# LasaurDriverBoard2.net
KiCad netlist of a schematic drawn in EAGLE
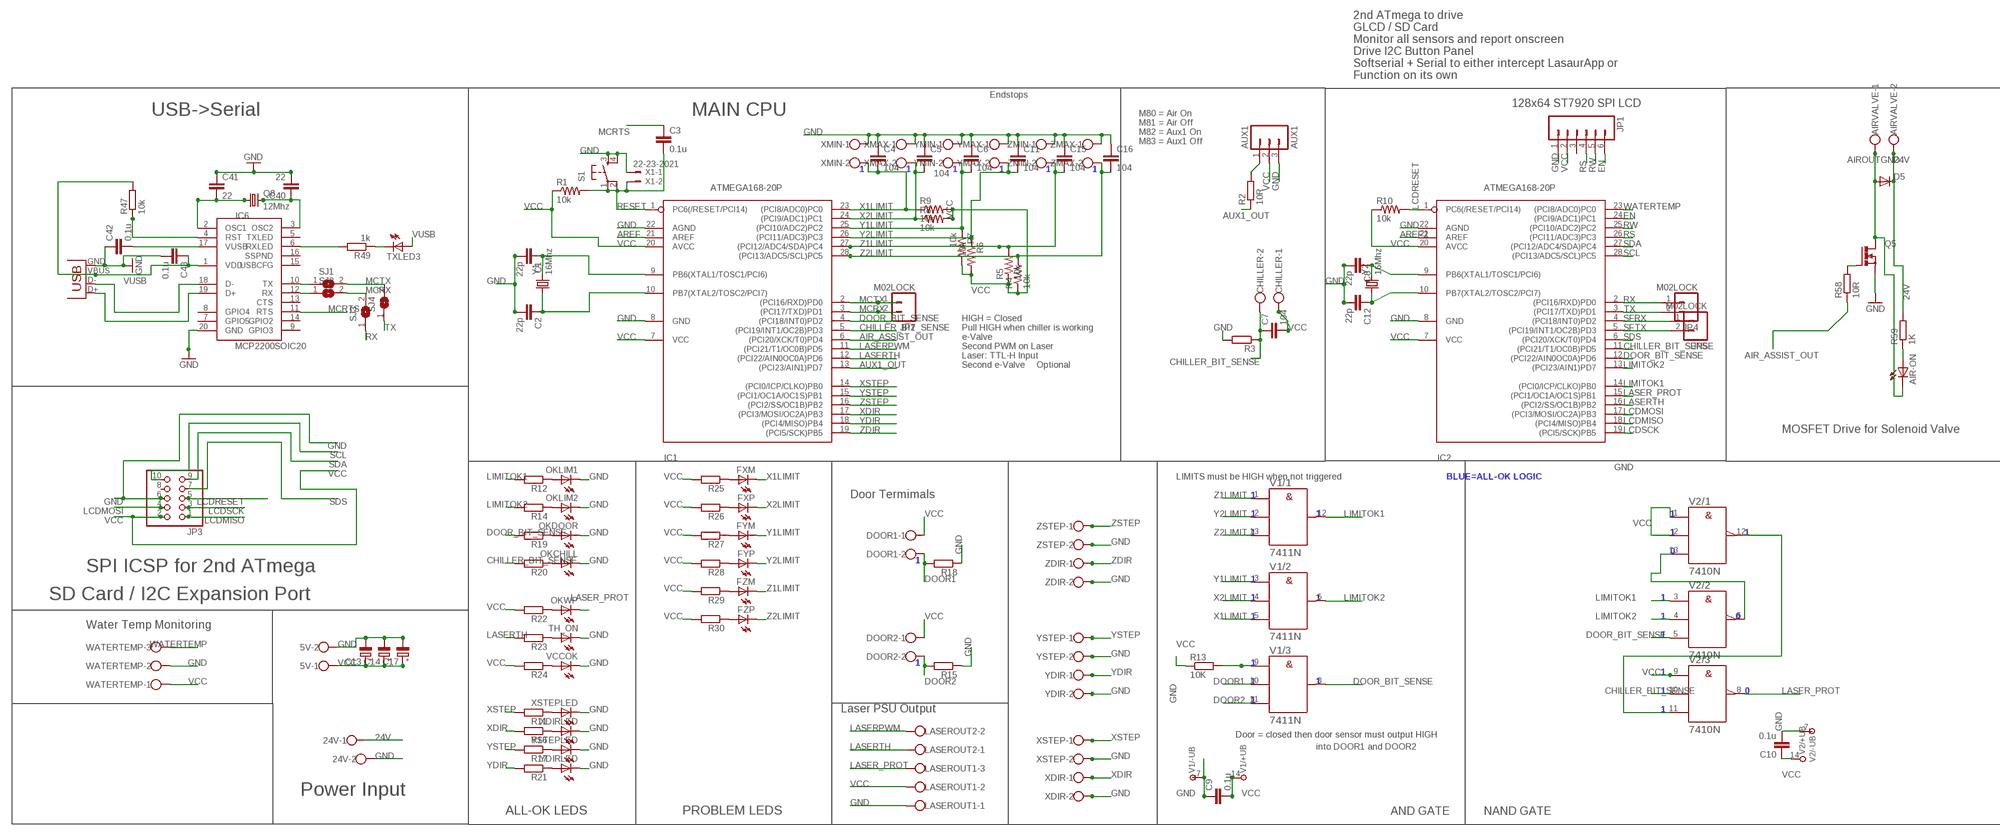
[diagram p0: schematic, sheet 1, part 1 of 2]
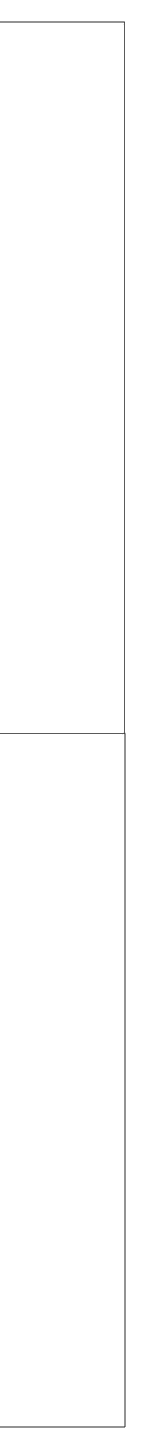
[diagram p1: schematic, sheet 1, part 2 of 2]

(export (version "E")
  (design (tool "Eeschema 10.0.6"))
  (components
    (comp (ref "5V")
      (value "W237-102")
      (footprint "eagle-import:W237-102")
      (fields (field (name "MPN") "237-102"))
      (libsource (lib "eagle-import") (part "W237-102"))
    )
    (comp (ref "24V")
      (value "W237-102")
      (footprint "eagle-import:W237-102")
      (fields (field (name "MPN") "237-102"))
      (libsource (lib "eagle-import") (part "W237-102"))
    )
    (comp (ref "AIR-ON")
      (value "LED3MM")
      (footprint "eagle-import:LED3MM")
      (libsource (lib "eagle-import") (part "LED3MM"))
    )
    (comp (ref "AIRVALVE")
      (value "W237-102")
      (footprint "eagle-import:W237-102")
      (fields (field (name "MPN") "237-102"))
      (libsource (lib "eagle-import") (part "W237-102"))
    )
    (comp (ref "AUX1")
      (value "AUX1")
      (footprint "eagle-import:MOLEX-1X3")
      (libsource (lib "eagle-import") (part "M03POLAR"))
    )
    (comp (ref "C1")
      (value "22p")
      (footprint "eagle-import:1206")
      (libsource (lib "eagle-import") (part "CAP1206"))
    )
    (comp (ref "C2")
      (value "22p")
      (footprint "eagle-import:1206")
      (libsource (lib "eagle-import") (part "CAP1206"))
    )
    (comp (ref "C3")
      (value "0.1u")
      (footprint "eagle-import:1206")
      (libsource (lib "eagle-import") (part "CAP1206"))
    )
    (comp (ref "C4")
      (value "104")
      (footprint "eagle-import:C1206")
      (libsource (lib "eagle-import") (part "C-EUC1206"))
    )
    (comp (ref "C5")
      (value "C-EUC1206")
      (footprint "eagle-import:C1206")
      (libsource (lib "eagle-import") (part "C-EUC1206"))
    )
    (comp (ref "C6")
      (value "104")
      (footprint "eagle-import:C1206")
      (libsource (lib "eagle-import") (part "C-EUC1206"))
    )
    (comp (ref "C7")
      (value "104")
      (footprint "eagle-import:C1206")
      (libsource (lib "eagle-import") (part "C-EUC1206"))
    )
    (comp (ref "C8")
      (value "22p")
      (footprint "eagle-import:1206")
      (libsource (lib "eagle-import") (part "CAP1206"))
    )
    (comp (ref "C9")
      (value "0.1u")
      (footprint "eagle-import:1206")
      (libsource (lib "eagle-import") (part "CAP1206"))
    )
    (comp (ref "C10")
      (value "0.1u")
      (footprint "eagle-import:1206")
      (libsource (lib "eagle-import") (part "CAP1206"))
    )
    (comp (ref "C11")
      (value "104")
      (footprint "eagle-import:C1206")
      (libsource (lib "eagle-import") (part "C-EUC1206"))
    )
    (comp (ref "C12")
      (value "22p")
      (footprint "eagle-import:1206")
      (libsource (lib "eagle-import") (part "CAP1206"))
    )
    (comp (ref "C13")
      (value "CPOL-EUB")
      (footprint "eagle-import:PANASONIC_B")
      (libsource (lib "eagle-import") (part "CPOL-EUB"))
    )
    (comp (ref "C14")
      (value "CPOL-EUB")
      (footprint "eagle-import:PANASONIC_B")
      (libsource (lib "eagle-import") (part "CPOL-EUB"))
    )
    (comp (ref "C15")
      (value "104")
      (footprint "eagle-import:C1206")
      (libsource (lib "eagle-import") (part "C-EUC1206"))
    )
    (comp (ref "C16")
      (value "104")
      (footprint "eagle-import:C1206")
      (libsource (lib "eagle-import") (part "C-EUC1206"))
    )
    (comp (ref "C17")
      (value "CPOL-EUB")
      (footprint "eagle-import:PANASONIC_B")
      (libsource (lib "eagle-import") (part "CPOL-EUB"))
    )
    (comp (ref "C40")
      (value "22")
      (footprint "eagle-import:1206")
      (libsource (lib "eagle-import") (part "CAP1206"))
    )
    (comp (ref "C41")
      (value "22")
      (footprint "eagle-import:1206")
      (libsource (lib "eagle-import") (part "CAP1206"))
    )
    (comp (ref "C42")
      (value "0.1u")
      (footprint "eagle-import:1206")
      (libsource (lib "eagle-import") (part "CAP1206"))
    )
    (comp (ref "C43")
      (value "0.1u")
      (footprint "eagle-import:1206")
      (libsource (lib "eagle-import") (part "CAP1206"))
    )
    (comp (ref "CHILLER")
      (value "W237-102")
      (footprint "eagle-import:W237-102")
      (fields (field (name "MPN") "237-102"))
      (libsource (lib "eagle-import") (part "W237-102"))
    )
    (comp (ref "D5")
      (value "DIODESMA-ALT")
      (footprint "eagle-import:SMA-DIODE_ALT")
      (libsource (lib "eagle-import") (part "DIODESMA-ALT"))
    )
    (comp (ref "DOOR1")
      (value "W237-102")
      (footprint "eagle-import:W237-102")
      (fields (field (name "MPN") "237-102"))
      (libsource (lib "eagle-import") (part "W237-102"))
    )
    (comp (ref "DOOR2")
      (value "W237-102")
      (footprint "eagle-import:W237-102")
      (fields (field (name "MPN") "237-102"))
      (libsource (lib "eagle-import") (part "W237-102"))
    )
    (comp (ref "FXM")
      (value "LED3MM")
      (footprint "eagle-import:LED3MM")
      (libsource (lib "eagle-import") (part "led_LED3MM"))
    )
    (comp (ref "FXP")
      (value "LED3MM")
      (footprint "eagle-import:LED3MM")
      (libsource (lib "eagle-import") (part "led_LED3MM"))
    )
    (comp (ref "FYM")
      (value "LED3MM")
      (footprint "eagle-import:LED3MM")
      (libsource (lib "eagle-import") (part "led_LED3MM"))
    )
    (comp (ref "FYP")
      (value "LED3MM")
      (footprint "eagle-import:LED3MM")
      (libsource (lib "eagle-import") (part "led_LED3MM"))
    )
    (comp (ref "FZM")
      (value "LED3MM")
      (footprint "eagle-import:LED3MM")
      (libsource (lib "eagle-import") (part "led_LED3MM"))
    )
    (comp (ref "FZP")
      (value "LED3MM")
      (footprint "eagle-import:LED3MM")
      (libsource (lib "eagle-import") (part "led_LED3MM"))
    )
    (comp (ref "IC1")
      (value "ATMEGA168-20P")
      (footprint "eagle-import:DIL28-3")
      (libsource (lib "eagle-import") (part "ATMEGA168P-20"))
    )
    (comp (ref "IC2")
      (value "ATMEGA168-20P")
      (footprint "eagle-import:DIL28-3")
      (libsource (lib "eagle-import") (part "ATMEGA168P-20"))
    )
    (comp (ref "IC6")
      (value "MCP2200SOIC20")
      (footprint "eagle-import:SOIC20")
      (libsource (lib "eagle-import") (part "MCP2200SOIC20"))
    )
    (comp (ref "JP1")
      (value "M06LOCK")
      (footprint "eagle-import:1X06_LOCK")
      (libsource (lib "eagle-import") (part "M06LOCK"))
    )
    (comp (ref "JP2")
      (value "M02LOCK")
      (footprint "eagle-import:1X02_LOCK")
      (libsource (lib "eagle-import") (part "M02LOCK"))
    )
    (comp (ref "JP3")
      (value "PINHD-2X5")
      (footprint "eagle-import:2X05")
      (libsource (lib "eagle-import") (part "PINHD-2X5"))
    )
    (comp (ref "JP4")
      (value "M02LOCK")
      (footprint "eagle-import:1X02_LOCK")
      (libsource (lib "eagle-import") (part "M02LOCK"))
    )
    (comp (ref "JP5")
      (value "M02LOCK")
      (footprint "eagle-import:1X02_LOCK")
      (libsource (lib "eagle-import") (part "M02LOCK"))
    )
    (comp (ref "LASEROUT1")
      (value "W237-103")
      (footprint "eagle-import:W237-103")
      (fields (field (name "MPN") "237-103"))
      (libsource (lib "eagle-import") (part "W237-103"))
    )
    (comp (ref "LASEROUT2")
      (value "W237-102")
      (footprint "eagle-import:W237-102")
      (fields (field (name "MPN") "237-102"))
      (libsource (lib "eagle-import") (part "W237-102"))
    )
    (comp (ref "OKCHILL")
      (value "LED3MM")
      (footprint "eagle-import:LED3MM")
      (libsource (lib "eagle-import") (part "led_LED3MM"))
    )
    (comp (ref "OKDOOR")
      (value "LED3MM")
      (footprint "eagle-import:LED3MM")
      (libsource (lib "eagle-import") (part "led_LED3MM"))
    )
    (comp (ref "OKLIM1")
      (value "LED3MM")
      (footprint "eagle-import:LED3MM")
      (libsource (lib "eagle-import") (part "led_LED3MM"))
    )
    (comp (ref "OKLIM2")
      (value "LED3MM")
      (footprint "eagle-import:LED3MM")
      (libsource (lib "eagle-import") (part "led_LED3MM"))
    )
    (comp (ref "OKWP")
      (value "LED3MM")
      (footprint "eagle-import:LED3MM")
      (libsource (lib "eagle-import") (part "led_LED3MM"))
    )
    (comp (ref "Q5")
      (value "PMOSFET_NTO220BV")
      (footprint "eagle-import:TO220BV")
      (libsource (lib "eagle-import") (part "PMOSFET_NTO220BV"))
    )
    (comp (ref "Q8")
      (value "12Mhz")
      (footprint "eagle-import:HC49UP")
      (libsource (lib "eagle-import") (part "CRYSTALHC49UP"))
    )
    (comp (ref "R1")
      (value "10k")
      (footprint "eagle-import:M1206")
      (libsource (lib "eagle-import") (part "resistor_R-US_M1206"))
    )
    (comp (ref "R2")
      (value "10R")
      (footprint "eagle-import:M1206")
      (libsource (lib "eagle-import") (part "R-EU_M1206"))
    )
    (comp (ref "R3")
      (value "R-EU_M1206")
      (footprint "eagle-import:M1206")
      (libsource (lib "eagle-import") (part "R-EU_M1206"))
    )
    (comp (ref "R4")
      (value "10k")
      (footprint "eagle-import:M1206")
      (libsource (lib "eagle-import") (part "R-US_M1206"))
    )
    (comp (ref "R5")
      (value "10k")
      (footprint "eagle-import:M1206")
      (libsource (lib "eagle-import") (part "R-US_M1206"))
    )
    (comp (ref "R6")
      (value "10k")
      (footprint "eagle-import:M1206")
      (libsource (lib "eagle-import") (part "R-US_M1206"))
    )
    (comp (ref "R7")
      (value "10k")
      (footprint "eagle-import:M1206")
      (libsource (lib "eagle-import") (part "R-US_M1206"))
    )
    (comp (ref "R8")
      (value "10k")
      (footprint "eagle-import:M1206")
      (libsource (lib "eagle-import") (part "R-US_M1206"))
    )
    (comp (ref "R9")
      (value "10k")
      (footprint "eagle-import:M1206")
      (libsource (lib "eagle-import") (part "R-US_M1206"))
    )
    (comp (ref "R10")
      (value "10k")
      (footprint "eagle-import:M1206")
      (libsource (lib "eagle-import") (part "resistor_R-US_M1206"))
    )
    (comp (ref "R11")
      (value "R-EU_M1206")
      (footprint "eagle-import:M1206")
      (libsource (lib "eagle-import") (part "R-EU_M1206"))
    )
    (comp (ref "R12")
      (value "R-EU_M1206")
      (footprint "eagle-import:M1206")
      (libsource (lib "eagle-import") (part "R-EU_M1206"))
    )
    (comp (ref "R13")
      (value "10K")
      (footprint "eagle-import:M1206")
      (libsource (lib "eagle-import") (part "R-EU_M1206"))
    )
    (comp (ref "R14")
      (value "R-EU_M1206")
      (footprint "eagle-import:M1206")
      (libsource (lib "eagle-import") (part "R-EU_M1206"))
    )
    (comp (ref "R15")
      (value "R-EU_M1206")
      (footprint "eagle-import:M1206")
      (libsource (lib "eagle-import") (part "R-EU_M1206"))
    )
    (comp (ref "R16")
      (value "R-EU_M1206")
      (footprint "eagle-import:M1206")
      (libsource (lib "eagle-import") (part "R-EU_M1206"))
    )
    (comp (ref "R17")
      (value "R-EU_M1206")
      (footprint "eagle-import:M1206")
      (libsource (lib "eagle-import") (part "R-EU_M1206"))
    )
    (comp (ref "R18")
      (value "R-EU_M1206")
      (footprint "eagle-import:M1206")
      (libsource (lib "eagle-import") (part "R-EU_M1206"))
    )
    (comp (ref "R19")
      (value "R-EU_M1206")
      (footprint "eagle-import:M1206")
      (libsource (lib "eagle-import") (part "R-EU_M1206"))
    )
    (comp (ref "R20")
      (value "R-EU_M1206")
      (footprint "eagle-import:M1206")
      (libsource (lib "eagle-import") (part "R-EU_M1206"))
    )
    (comp (ref "R21")
      (value "R-EU_M1206")
      (footprint "eagle-import:M1206")
      (libsource (lib "eagle-import") (part "R-EU_M1206"))
    )
    (comp (ref "R22")
      (value "R-EU_M1206")
      (footprint "eagle-import:M1206")
      (libsource (lib "eagle-import") (part "R-EU_M1206"))
    )
    (comp (ref "R23")
      (value "R-EU_M1206")
      (footprint "eagle-import:M1206")
      (libsource (lib "eagle-import") (part "R-EU_M1206"))
    )
    (comp (ref "R24")
      (value "R-EU_M1206")
      (footprint "eagle-import:M1206")
      (libsource (lib "eagle-import") (part "R-EU_M1206"))
    )
    (comp (ref "R25")
      (value "R-EU_M1206")
      (footprint "eagle-import:M1206")
      (libsource (lib "eagle-import") (part "R-EU_M1206"))
    )
    (comp (ref "R26")
      (value "R-EU_M1206")
      (footprint "eagle-import:M1206")
      (libsource (lib "eagle-import") (part "R-EU_M1206"))
    )
    (comp (ref "R27")
      (value "R-EU_M1206")
      (footprint "eagle-import:M1206")
      (libsource (lib "eagle-import") (part "R-EU_M1206"))
    )
    (comp (ref "R28")
      (value "R-EU_M1206")
      (footprint "eagle-import:M1206")
      (libsource (lib "eagle-import") (part "R-EU_M1206"))
    )
    (comp (ref "R29")
      (value "R-EU_M1206")
      (footprint "eagle-import:M1206")
      (libsource (lib "eagle-import") (part "R-EU_M1206"))
    )
    (comp (ref "R30")
      (value "R-EU_M1206")
      (footprint "eagle-import:M1206")
      (libsource (lib "eagle-import") (part "R-EU_M1206"))
    )
    (comp (ref "R47")
      (value "10k")
      (footprint "eagle-import:M1206")
      (libsource (lib "eagle-import") (part "R-EU_M1206"))
    )
    (comp (ref "R49")
      (value "1k")
      (footprint "eagle-import:M1206")
      (libsource (lib "eagle-import") (part "R-EU_M1206"))
    )
    (comp (ref "R58")
      (value "10R")
      (footprint "eagle-import:M1206")
      (libsource (lib "eagle-import") (part "R-EU_M1206"))
    )
    (comp (ref "R59")
      (value "1K")
      (footprint "eagle-import:M1206")
      (libsource (lib "eagle-import") (part "R-EU_M1206"))
    )
    (comp (ref "S1")
      (value "TAC_SWITCHPTH")
      (footprint "eagle-import:TACTILE-PTH")
      (libsource (lib "eagle-import") (part "TAC_SWITCHPTH"))
    )
    (comp (ref "SJ1") (value "SJ") (footprint "eagle-import:SJ") (libsource (lib "eagle-import") (part "SJ")))
    (comp (ref "SJ2") (value "SJ") (footprint "eagle-import:SJ") (libsource (lib "eagle-import") (part "SJ")))
    (comp (ref "SJ3") (value "SJ") (footprint "eagle-import:SJ") (libsource (lib "eagle-import") (part "SJ")))
    (comp (ref "SJ4") (value "SJ") (footprint "eagle-import:SJ") (libsource (lib "eagle-import") (part "SJ")))
    (comp (ref "TH_ON")
      (value "LED3MM")
      (footprint "eagle-import:LED3MM")
      (libsource (lib "eagle-import") (part "led_LED3MM"))
    )
    (comp (ref "TXLED3")
      (value "LEDSMT1206")
      (footprint "eagle-import:1206")
      (libsource (lib "eagle-import") (part "led_LEDSMT1206"))
    )
    (comp (ref "V1")
      (value "7411N")
      (footprint "eagle-import:DIL14")
      (libsource (lib "eagle-import") (part "7411N"))
    )
    (comp (ref "V2")
      (value "7410N")
      (footprint "eagle-import:DIL14")
      (libsource (lib "eagle-import") (part "7410N"))
    )
    (comp (ref "VCCOK")
      (value "LED3MM")
      (footprint "eagle-import:LED3MM")
      (libsource (lib "eagle-import") (part "led_LED3MM"))
    )
    (comp (ref "WATERTEMP")
      (value "W237-103")
      (footprint "eagle-import:W237-103")
      (fields (field (name "MPN") "237-103"))
      (libsource (lib "eagle-import") (part "W237-103"))
    )
    (comp (ref "X1")
      (value "22-23-2021")
      (footprint "eagle-import:22-23-2021")
      (fields (field (name "MF") "MOLEX"))
      (libsource (lib "eagle-import") (part "22-23-2021"))
    )
    (comp (ref "X3")
      (value "USB-SMD-NS")
      (footprint "eagle-import:USB-MINIB-NOSTOP")
      (libsource (lib "eagle-import") (part "USB-SMD-NS"))
    )
    (comp (ref "XDIR")
      (value "W237-102")
      (footprint "eagle-import:W237-102")
      (fields (field (name "MPN") "237-102"))
      (libsource (lib "eagle-import") (part "W237-102"))
    )
    (comp (ref "XDIRLED")
      (value "LED3MM")
      (footprint "eagle-import:LED3MM")
      (libsource (lib "eagle-import") (part "led_LED3MM"))
    )
    (comp (ref "XMAX")
      (value "W237-102")
      (footprint "eagle-import:W237-102")
      (fields (field (name "MPN") "237-102"))
      (libsource (lib "eagle-import") (part "W237-102"))
    )
    (comp (ref "XMIN")
      (value "W237-102")
      (footprint "eagle-import:W237-102")
      (fields (field (name "MPN") "237-102"))
      (libsource (lib "eagle-import") (part "W237-102"))
    )
    (comp (ref "XSTEP")
      (value "W237-102")
      (footprint "eagle-import:W237-102")
      (fields (field (name "MPN") "237-102"))
      (libsource (lib "eagle-import") (part "W237-102"))
    )
    (comp (ref "XSTEPLED")
      (value "LED3MM")
      (footprint "eagle-import:LED3MM")
      (libsource (lib "eagle-import") (part "led_LED3MM"))
    )
    (comp (ref "Y1")
      (value "16Mhz")
      (footprint "eagle-import:HC49UP")
      (libsource (lib "eagle-import") (part "CRYSTALSMD"))
    )
    (comp (ref "Y2")
      (value "16Mhz")
      (footprint "eagle-import:HC49UP")
      (libsource (lib "eagle-import") (part "CRYSTALSMD"))
    )
    (comp (ref "YDIR")
      (value "W237-102")
      (footprint "eagle-import:W237-102")
      (fields (field (name "MPN") "237-102"))
      (libsource (lib "eagle-import") (part "W237-102"))
    )
    (comp (ref "YDIRLED")
      (value "LED3MM")
      (footprint "eagle-import:LED3MM")
      (libsource (lib "eagle-import") (part "led_LED3MM"))
    )
    (comp (ref "YMAX")
      (value "W237-102")
      (footprint "eagle-import:W237-102")
      (fields (field (name "MPN") "237-102"))
      (libsource (lib "eagle-import") (part "W237-102"))
    )
    (comp (ref "YMIN")
      (value "104")
      (footprint "eagle-import:W237-102")
      (fields (field (name "MPN") "237-102"))
      (libsource (lib "eagle-import") (part "W237-102"))
    )
    (comp (ref "YSTEP")
      (value "W237-102")
      (footprint "eagle-import:W237-102")
      (fields (field (name "MPN") "237-102"))
      (libsource (lib "eagle-import") (part "W237-102"))
    )
    (comp (ref "YSTEPLED")
      (value "LED3MM")
      (footprint "eagle-import:LED3MM")
      (libsource (lib "eagle-import") (part "led_LED3MM"))
    )
    (comp (ref "ZDIR")
      (value "W237-102")
      (footprint "eagle-import:W237-102")
      (fields (field (name "MPN") "237-102"))
      (libsource (lib "eagle-import") (part "W237-102"))
    )
    (comp (ref "ZMAX")
      (value "W237-102")
      (footprint "eagle-import:W237-102")
      (fields (field (name "MPN") "237-102"))
      (libsource (lib "eagle-import") (part "W237-102"))
    )
    (comp (ref "ZMIN")
      (value "W237-102")
      (footprint "eagle-import:W237-102")
      (fields (field (name "MPN") "237-102"))
      (libsource (lib "eagle-import") (part "W237-102"))
    )
    (comp (ref "ZSTEP")
      (value "W237-102")
      (footprint "eagle-import:W237-102")
      (fields (field (name "MPN") "237-102"))
      (libsource (lib "eagle-import") (part "W237-102"))
    )
  )
  (nets
    (net (code "1") (name "/24V") (class "Default")
      (node (ref "24V") (pin "1") (pinfunction "KL_1") (pintype "passive"))
      (node (ref "AIRVALVE") (pin "2") (pinfunction "KL_2") (pintype "passive"))
      (node (ref "D5") (pin "C") (pinfunction "C_C") (pintype "passive"))
      (node (ref "R59") (pin "2") (pinfunction "2_2") (pintype "passive"))
    )
    (net (code "2") (name "/AIROUTGND") (class "Default")
      (node (ref "AIR-ON") (pin "K") (pinfunction "C_K") (pintype "passive"))
      (node (ref "AIRVALVE") (pin "1") (pinfunction "KL_1") (pintype "passive"))
      (node (ref "D5") (pin "A") (pinfunction "A_A") (pintype "passive"))
      (node (ref "Q5") (pin "D") (pinfunction "D_D") (pintype "passive"))
    )
    (net (code "3") (name "/AIR_ASSIST_OUT") (class "Default")
      (node (ref "IC1") (pin "6") (pinfunction "(PCI20/XCK/T0)PD4_6") (pintype "bidirectional"))
      (node (ref "R58") (pin "1") (pinfunction "1_1") (pintype "passive"))
    )
    (net (code "4") (name "/AREF") (class "Default")
      (node (ref "IC1") (pin "21") (pinfunction "AREF_21") (pintype "bidirectional"))
    )
    (net (code "5") (name "/AREF2") (class "Default")
      (node (ref "IC2") (pin "21") (pinfunction "AREF_21") (pintype "bidirectional"))
    )
    (net (code "6") (name "/AUX1_OUT") (class "Default")
      (node (ref "IC1") (pin "13") (pinfunction "(PCI23/AIN1)PD7_13") (pintype "bidirectional"))
      (node (ref "R2") (pin "1") (pinfunction "1_1") (pintype "passive"))
    )
    (net (code "7") (name "/CHILLER_BIT_SENSE") (class "Default")
      (node (ref "C7") (pin "1") (pinfunction "1_1") (pintype "passive"))
      (node (ref "CHILLER") (pin "2") (pinfunction "KL_2") (pintype "passive"))
      (node (ref "IC1") (pin "5") (pinfunction "(PCI19/INT1/OC2B)PD3_5") (pintype "bidirectional"))
      (node (ref "IC2") (pin "11") (pinfunction "(PCI21/T1/OC0B)PD5_11") (pintype "bidirectional"))
      (node (ref "R20") (pin "2") (pinfunction "2_2") (pintype "passive"))
      (node (ref "R3") (pin "1") (pinfunction "1_1") (pintype "passive"))
      (node (ref "V2") (pin "10") (pinfunction "B_10") (pintype "input"))
    )
    (net (code "8") (name "/DOOR1") (class "Default")
      (node (ref "DOOR1") (pin "2") (pinfunction "KL_2") (pintype "passive"))
      (node (ref "R18") (pin "2") (pinfunction "2_2") (pintype "passive"))
      (node (ref "V1") (pin "10") (pinfunction "B_10") (pintype "input"))
    )
    (net (code "9") (name "/DOOR2") (class "Default")
      (node (ref "DOOR2") (pin "2") (pinfunction "KL_2") (pintype "passive"))
      (node (ref "R15") (pin "2") (pinfunction "2_2") (pintype "passive"))
      (node (ref "V1") (pin "11") (pinfunction "C_11") (pintype "input"))
    )
    (net (code "10") (name "/DOOR_BIT_SENSE") (class "Default")
      (node (ref "IC1") (pin "4") (pinfunction "(PCI18/INT0)PD2_4") (pintype "bidirectional"))
      (node (ref "IC2") (pin "12") (pinfunction "(PCI22/AIN0OC0A)PD6_12") (pintype "bidirectional"))
      (node (ref "R19") (pin "2") (pinfunction "2_2") (pintype "passive"))
      (node (ref "V1") (pin "8") (pinfunction "Y_8") (pintype "output"))
      (node (ref "V2") (pin "5") (pinfunction "C_5") (pintype "input"))
    )
    (net (code "11") (name "/EN") (class "Default")
      (node (ref "IC2") (pin "24") (pinfunction "(PCI9/ADC1)PC1_24") (pintype "bidirectional"))
      (node (ref "JP1") (pin "6") (pinfunction "6_6") (pintype "passive"))
    )
    (net (code "12") (name "/LASERPWM") (class "Default")
      (node (ref "IC1") (pin "11") (pinfunction "(PCI21/T1/OC0B)PD5_11") (pintype "bidirectional"))
      (node (ref "LASEROUT2") (pin "2") (pinfunction "KL_2") (pintype "passive"))
    )
    (net (code "13") (name "/LASERTH") (class "Default")
      (node (ref "IC1") (pin "12") (pinfunction "(PCI22/AIN0OC0A)PD6_12") (pintype "bidirectional"))
      (node (ref "IC2") (pin "16") (pinfunction "(PCI2/SS/OC1B)PB2_16") (pintype "bidirectional"))
      (node (ref "LASEROUT2") (pin "1") (pinfunction "KL_1") (pintype "passive"))
      (node (ref "R23") (pin "2") (pinfunction "2_2") (pintype "passive"))
    )
    (net (code "14") (name "/LASER_PROT") (class "Default")
      (node (ref "IC2") (pin "15") (pinfunction "(PCI1/OC1A/OC1S)PB1_15") (pintype "bidirectional"))
      (node (ref "LASEROUT1") (pin "3") (pinfunction "KL_3") (pintype "passive"))
      (node (ref "OKWP") (pin "K") (pinfunction "C_K") (pintype "passive"))
      (node (ref "V2") (pin "8") (pinfunction "Y_8") (pintype "output"))
    )
    (net (code "15") (name "/LCDMISO") (class "Default")
      (node (ref "IC2") (pin "18") (pinfunction "(PCI4/MISO)PB4_18") (pintype "bidirectional"))
      (node (ref "JP3") (pin "1") (pinfunction "1_1") (pintype "passive"))
    )
    (net (code "16") (name "/LCDMOSI") (class "Default")
      (node (ref "IC2") (pin "17") (pinfunction "(PCI3/MOSI/OC2A)PB3_17") (pintype "bidirectional"))
      (node (ref "JP3") (pin "4") (pinfunction "4_4") (pintype "passive"))
    )
    (net (code "17") (name "/LCDRESET") (class "Default")
      (node (ref "IC2") (pin "1") (pinfunction "PC6(/RESET/PCI14)_1") (pintype "bidirectional"))
      (node (ref "JP3") (pin "5") (pinfunction "5_5") (pintype "passive"))
      (node (ref "R10") (pin "2") (pinfunction "2_2") (pintype "passive"))
    )
    (net (code "18") (name "/LCDSCK") (class "Default")
      (node (ref "IC2") (pin "19") (pinfunction "(PCI5/SCK)PB5_19") (pintype "bidirectional"))
      (node (ref "JP3") (pin "3") (pinfunction "3_3") (pintype "passive"))
    )
    (net (code "19") (name "/LIMITOK1") (class "Default")
      (node (ref "IC2") (pin "14") (pinfunction "(PCI0/ICP/CLKO)PB0_14") (pintype "bidirectional"))
      (node (ref "R12") (pin "2") (pinfunction "2_2") (pintype "passive"))
      (node (ref "V1") (pin "12") (pinfunction "Y_12") (pintype "output"))
      (node (ref "V2") (pin "3") (pinfunction "A_3") (pintype "input"))
    )
    (net (code "20") (name "/LIMITOK2") (class "Default")
      (node (ref "IC2") (pin "13") (pinfunction "(PCI23/AIN1)PD7_13") (pintype "bidirectional"))
      (node (ref "R14") (pin "2") (pinfunction "2_2") (pintype "passive"))
      (node (ref "V1") (pin "6") (pinfunction "Y_6") (pintype "output"))
      (node (ref "V2") (pin "4") (pinfunction "B_4") (pintype "input"))
    )
    (net (code "21") (name "/MCRTS") (class "Default")
      (node (ref "C3") (pin "1") (pinfunction "1_1") (pintype "passive"))
      (node (ref "IC6") (pin "11") (pinfunction "RTS_11") (pintype "bidirectional"))
    )
    (net (code "22") (name "/MCRX") (class "Default")
      (node (ref "IC1") (pin "3") (pinfunction "(PCI17/TXD)PD1_3") (pintype "bidirectional"))
      (node (ref "JP2") (pin "2") (pinfunction "2_2") (pintype "passive"))
      (node (ref "SJ2") (pin "2") (pinfunction "2_2") (pintype "passive"))
      (node (ref "SJ3") (pin "2") (pinfunction "2_2") (pintype "passive"))
    )
    (net (code "23") (name "/MCTX") (class "Default")
      (node (ref "IC1") (pin "2") (pinfunction "(PCI16/RXD)PD0_2") (pintype "bidirectional"))
      (node (ref "JP2") (pin "1") (pinfunction "1_1") (pintype "passive"))
      (node (ref "SJ1") (pin "2") (pinfunction "2_2") (pintype "passive"))
      (node (ref "SJ4") (pin "2") (pinfunction "2_2") (pintype "passive"))
    )
    (net (code "24") (name "/RESET") (class "Default")
      (node (ref "C3") (pin "2") (pinfunction "2_2") (pintype "passive"))
      (node (ref "IC1") (pin "1") (pinfunction "PC6(/RESET/PCI14)_1") (pintype "bidirectional"))
      (node (ref "R1") (pin "2") (pinfunction "2_2") (pintype "passive"))
      (node (ref "S1") (pin "1") (pinfunction "1_1") (pintype "passive"))
      (node (ref "S1") (pin "2") (pinfunction "2_2") (pintype "passive"))
      (node (ref "X1") (pin "2") (pinfunction "S_2") (pintype "passive"))
    )
    (net (code "25") (name "/RS") (class "Default")
      (node (ref "IC2") (pin "26") (pinfunction "(PCI11/ADC3)PC3_26") (pintype "bidirectional"))
      (node (ref "JP1") (pin "4") (pinfunction "4_4") (pintype "passive"))
    )
    (net (code "26") (name "/RW") (class "Default")
      (node (ref "IC2") (pin "25") (pinfunction "(PCI10/ADC2)PC2_25") (pintype "bidirectional"))
      (node (ref "JP1") (pin "5") (pinfunction "5_5") (pintype "passive"))
    )
    (net (code "27") (name "/RX") (class "Default")
      (node (ref "IC2") (pin "2") (pinfunction "(PCI16/RXD)PD0_2") (pintype "bidirectional"))
      (node (ref "JP4") (pin "1") (pinfunction "1_1") (pintype "passive"))
      (node (ref "SJ3") (pin "1") (pinfunction "1_1") (pintype "passive"))
    )
    (net (code "28") (name "/SCL") (class "Default")
      (node (ref "IC2") (pin "28") (pinfunction "(PCI13/ADC5/SCL)PC5_28") (pintype "bidirectional"))
      (node (ref "JP3") (pin "10") (pinfunction "10_10") (pintype "passive"))
    )
    (net (code "29") (name "/SDA") (class "Default")
      (node (ref "IC2") (pin "27") (pinfunction "(PCI12/ADC4/SDA)PC4_27") (pintype "bidirectional"))
      (node (ref "JP3") (pin "9") (pinfunction "9_9") (pintype "passive"))
    )
    (net (code "30") (name "/SDS") (class "Default")
      (node (ref "IC2") (pin "6") (pinfunction "(PCI20/XCK/T0)PD4_6") (pintype "bidirectional"))
      (node (ref "JP3") (pin "7") (pinfunction "7_7") (pintype "passive"))
    )
    (net (code "31") (name "/SFRX") (class "Default")
      (node (ref "IC2") (pin "4") (pinfunction "(PCI18/INT0)PD2_4") (pintype "bidirectional"))
      (node (ref "JP5") (pin "1") (pinfunction "1_1") (pintype "passive"))
    )
    (net (code "32") (name "/SFTX") (class "Default")
      (node (ref "IC2") (pin "5") (pinfunction "(PCI19/INT1/OC2B)PD3_5") (pintype "bidirectional"))
      (node (ref "JP5") (pin "2") (pinfunction "2_2") (pintype "passive"))
    )
    (net (code "33") (name "/TX") (class "Default")
      (node (ref "IC2") (pin "3") (pinfunction "(PCI17/TXD)PD1_3") (pintype "bidirectional"))
      (node (ref "JP4") (pin "2") (pinfunction "2_2") (pintype "passive"))
      (node (ref "SJ4") (pin "1") (pinfunction "1_1") (pintype "passive"))
    )
    (net (code "34") (name "/VCC") (class "Default")
      (node (ref "5V") (pin "1") (pinfunction "KL_1") (pintype "passive"))
      (node (ref "AUX1") (pin "2") (pinfunction "2_2") (pintype "passive"))
      (node (ref "C10") (pin "1") (pinfunction "1_1") (pintype "passive"))
      (node (ref "C13") (pin "+") (pinfunction "+_+") (pintype "passive"))
      (node (ref "C14") (pin "+") (pinfunction "+_+") (pintype "passive"))
      (node (ref "C17") (pin "+") (pinfunction "+_+") (pintype "passive"))
      (node (ref "C7") (pin "2") (pinfunction "2_2") (pintype "passive"))
      (node (ref "C9") (pin "2") (pinfunction "2_2") (pintype "passive"))
      (node (ref "CHILLER") (pin "1") (pinfunction "KL_1") (pintype "passive"))
      (node (ref "DOOR1") (pin "1") (pinfunction "KL_1") (pintype "passive"))
      (node (ref "DOOR2") (pin "1") (pinfunction "KL_1") (pintype "passive"))
      (node (ref "IC1") (pin "20") (pinfunction "AVCC_20") (pintype "bidirectional"))
      (node (ref "IC1") (pin "7") (pinfunction "VCC_7") (pintype "bidirectional"))
      (node (ref "IC2") (pin "20") (pinfunction "AVCC_20") (pintype "bidirectional"))
      (node (ref "IC2") (pin "7") (pinfunction "VCC_7") (pintype "bidirectional"))
      (node (ref "JP1") (pin "2") (pinfunction "2_2") (pintype "passive"))
      (node (ref "JP3") (pin "2") (pinfunction "2_2") (pintype "passive"))
      (node (ref "LASEROUT1") (pin "2") (pinfunction "KL_2") (pintype "passive"))
      (node (ref "R1") (pin "1") (pinfunction "1_1") (pintype "passive"))
      (node (ref "R10") (pin "1") (pinfunction "1_1") (pintype "passive"))
      (node (ref "R13") (pin "1") (pinfunction "1_1") (pintype "passive"))
      (node (ref "R22") (pin "2") (pinfunction "2_2") (pintype "passive"))
      (node (ref "R24") (pin "2") (pinfunction "2_2") (pintype "passive"))
      (node (ref "R25") (pin "2") (pinfunction "2_2") (pintype "passive"))
      (node (ref "R26") (pin "2") (pinfunction "2_2") (pintype "passive"))
      (node (ref "R27") (pin "2") (pinfunction "2_2") (pintype "passive"))
      (node (ref "R28") (pin "2") (pinfunction "2_2") (pintype "passive"))
      (node (ref "R29") (pin "2") (pinfunction "2_2") (pintype "passive"))
      (node (ref "R30") (pin "2") (pinfunction "2_2") (pintype "passive"))
      (node (ref "R4") (pin "1") (pinfunction "1_1") (pintype "passive"))
      (node (ref "R5") (pin "1") (pinfunction "1_1") (pintype "passive"))
      (node (ref "R6") (pin "2") (pinfunction "2_2") (pintype "passive"))
      (node (ref "R7") (pin "2") (pinfunction "2_2") (pintype "passive"))
      (node (ref "R8") (pin "2") (pinfunction "2_2") (pintype "passive"))
      (node (ref "R9") (pin "2") (pinfunction "2_2") (pintype "passive"))
      (node (ref "V1") (pin "14") (pinfunction "+UB_14") (pintype "power_in"))
      (node (ref "V2") (pin "1") (pinfunction "A_1") (pintype "input"))
      (node (ref "V2") (pin "14") (pinfunction "+UB_14") (pintype "power_in"))
      (node (ref "V2") (pin "2") (pinfunction "B_2") (pintype "input"))
      (node (ref "V2") (pin "9") (pinfunction "A_9") (pintype "input"))
      (node (ref "WATERTEMP") (pin "1") (pinfunction "KL_1") (pintype "passive"))
    )
    (net (code "35") (name "/VUSB") (class "Default")
      (node (ref "C43") (pin "1") (pinfunction "1_1") (pintype "passive"))
      (node (ref "IC6") (pin "1") (pinfunction "VDD_1") (pintype "bidirectional"))
      (node (ref "R47") (pin "2") (pinfunction "2_2") (pintype "passive"))
      (node (ref "TXLED3") (pin "A") (pinfunction "A_A") (pintype "passive"))
      (node (ref "X3") (pin "VBUS") (pinfunction "VBUS_VBUS") (pintype "bidirectional"))
    )
    (net (code "36") (name "/WATERTEMP") (class "Default")
      (node (ref "IC2") (pin "23") (pinfunction "(PCI8/ADC0)PC0_23") (pintype "bidirectional"))
      (node (ref "WATERTEMP") (pin "3") (pinfunction "KL_3") (pintype "passive"))
    )
    (net (code "37") (name "/X1LIMIT") (class "Default")
      (node (ref "C4") (pin "2") (pinfunction "2_2") (pintype "passive"))
      (node (ref "FXM") (pin "K") (pinfunction "C_K") (pintype "passive"))
      (node (ref "IC1") (pin "23") (pinfunction "(PCI8/ADC0)PC0_23") (pintype "bidirectional"))
      (node (ref "R9") (pin "1") (pinfunction "1_1") (pintype "passive"))
      (node (ref "V1") (pin "5") (pinfunction "C_5") (pintype "input"))
      (node (ref "XMIN") (pin "2") (pinfunction "KL_2") (pintype "passive"))
    )
    (net (code "38") (name "/X2LIMIT") (class "Default")
      (node (ref "C5") (pin "2") (pinfunction "2_2") (pintype "passive"))
      (node (ref "FXP") (pin "K") (pinfunction "C_K") (pintype "passive"))
      (node (ref "IC1") (pin "24") (pinfunction "(PCI9/ADC1)PC1_24") (pintype "bidirectional"))
      (node (ref "R8") (pin "1") (pinfunction "1_1") (pintype "passive"))
      (node (ref "V1") (pin "4") (pinfunction "B_4") (pintype "input"))
      (node (ref "XMAX") (pin "2") (pinfunction "KL_2") (pintype "passive"))
    )
    (net (code "39") (name "/XDIR") (class "Default")
      (node (ref "IC1") (pin "17") (pinfunction "(PCI3/MOSI/OC2A)PB3_17") (pintype "bidirectional"))
      (node (ref "R16") (pin "2") (pinfunction "2_2") (pintype "passive"))
      (node (ref "XDIR") (pin "1") (pinfunction "KL_1") (pintype "passive"))
    )
    (net (code "40") (name "/XSTEP") (class "Default")
      (node (ref "IC1") (pin "14") (pinfunction "(PCI0/ICP/CLKO)PB0_14") (pintype "bidirectional"))
      (node (ref "R11") (pin "2") (pinfunction "2_2") (pintype "passive"))
      (node (ref "XSTEP") (pin "1") (pinfunction "KL_1") (pintype "passive"))
    )
    (net (code "41") (name "/Y1LIMIT") (class "Default")
      (node (ref "C6") (pin "2") (pinfunction "2_2") (pintype "passive"))
      (node (ref "FYM") (pin "K") (pinfunction "C_K") (pintype "passive"))
      (node (ref "IC1") (pin "25") (pinfunction "(PCI10/ADC2)PC2_25") (pintype "bidirectional"))
      (node (ref "R7") (pin "1") (pinfunction "1_1") (pintype "passive"))
      (node (ref "V1") (pin "3") (pinfunction "A_3") (pintype "input"))
      (node (ref "YMIN") (pin "2") (pinfunction "KL_2") (pintype "passive"))
    )
    (net (code "42") (name "/Y2LIMIT") (class "Default")
      (node (ref "C11") (pin "2") (pinfunction "2_2") (pintype "passive"))
      (node (ref "FYP") (pin "K") (pinfunction "C_K") (pintype "passive"))
      (node (ref "IC1") (pin "26") (pinfunction "(PCI11/ADC3)PC3_26") (pintype "bidirectional"))
      (node (ref "R6") (pin "1") (pinfunction "1_1") (pintype "passive"))
      (node (ref "V1") (pin "2") (pinfunction "B_2") (pintype "input"))
      (node (ref "YMAX") (pin "2") (pinfunction "KL_2") (pintype "passive"))
    )
    (net (code "43") (name "/YDIR") (class "Default")
      (node (ref "IC1") (pin "18") (pinfunction "(PCI4/MISO)PB4_18") (pintype "bidirectional"))
      (node (ref "R21") (pin "2") (pinfunction "2_2") (pintype "passive"))
      (node (ref "YDIR") (pin "1") (pinfunction "KL_1") (pintype "passive"))
    )
    (net (code "44") (name "/YSTEP") (class "Default")
      (node (ref "IC1") (pin "15") (pinfunction "(PCI1/OC1A/OC1S)PB1_15") (pintype "bidirectional"))
      (node (ref "R17") (pin "2") (pinfunction "2_2") (pintype "passive"))
      (node (ref "YSTEP") (pin "1") (pinfunction "KL_1") (pintype "passive"))
    )
    (net (code "45") (name "/Z1LIMIT") (class "Default")
      (node (ref "C15") (pin "2") (pinfunction "2_2") (pintype "passive"))
      (node (ref "FZM") (pin "K") (pinfunction "C_K") (pintype "passive"))
      (node (ref "IC1") (pin "27") (pinfunction "(PCI12/ADC4/SDA)PC4_27") (pintype "bidirectional"))
      (node (ref "R5") (pin "2") (pinfunction "2_2") (pintype "passive"))
      (node (ref "V1") (pin "1") (pinfunction "A_1") (pintype "input"))
      (node (ref "ZMIN") (pin "2") (pinfunction "KL_2") (pintype "passive"))
    )
    (net (code "46") (name "/Z2LIMIT") (class "Default")
      (node (ref "C16") (pin "2") (pinfunction "2_2") (pintype "passive"))
      (node (ref "FZP") (pin "K") (pinfunction "C_K") (pintype "passive"))
      (node (ref "IC1") (pin "28") (pinfunction "(PCI13/ADC5/SCL)PC5_28") (pintype "bidirectional"))
      (node (ref "R4") (pin "2") (pinfunction "2_2") (pintype "passive"))
      (node (ref "V1") (pin "13") (pinfunction "C_13") (pintype "input"))
      (node (ref "ZMAX") (pin "2") (pinfunction "KL_2") (pintype "passive"))
    )
    (net (code "47") (name "/ZDIR") (class "Default")
      (node (ref "IC1") (pin "19") (pinfunction "(PCI5/SCK)PB5_19") (pintype "bidirectional"))
      (node (ref "ZDIR") (pin "1") (pinfunction "KL_1") (pintype "passive"))
    )
    (net (code "48") (name "/ZSTEP") (class "Default")
      (node (ref "IC1") (pin "16") (pinfunction "(PCI2/SS/OC1B)PB2_16") (pintype "bidirectional"))
      (node (ref "ZSTEP") (pin "1") (pinfunction "KL_1") (pintype "passive"))
    )
    (net (code "49") (name "GND") (class "Default")
      (node (ref "24V") (pin "2") (pinfunction "KL_2") (pintype "passive"))
      (node (ref "5V") (pin "2") (pinfunction "KL_2") (pintype "passive"))
      (node (ref "AUX1") (pin "3") (pinfunction "3_3") (pintype "passive"))
      (node (ref "C1") (pin "2") (pinfunction "2_2") (pintype "passive"))
      (node (ref "C10") (pin "2") (pinfunction "2_2") (pintype "passive"))
      (node (ref "C11") (pin "1") (pinfunction "1_1") (pintype "passive"))
      (node (ref "C12") (pin "2") (pinfunction "2_2") (pintype "passive"))
      (node (ref "C13") (pin "-") (pinfunction "-_-") (pintype "passive"))
      (node (ref "C14") (pin "-") (pinfunction "-_-") (pintype "passive"))
      (node (ref "C15") (pin "1") (pinfunction "1_1") (pintype "passive"))
      (node (ref "C16") (pin "1") (pinfunction "1_1") (pintype "passive"))
      (node (ref "C17") (pin "-") (pinfunction "-_-") (pintype "passive"))
      (node (ref "C2") (pin "2") (pinfunction "2_2") (pintype "passive"))
      (node (ref "C4") (pin "1") (pinfunction "1_1") (pintype "passive"))
      (node (ref "C40") (pin "2") (pinfunction "2_2") (pintype "passive"))
      (node (ref "C41") (pin "1") (pinfunction "1_1") (pintype "passive"))
      (node (ref "C42") (pin "1") (pinfunction "1_1") (pintype "passive"))
      (node (ref "C43") (pin "2") (pinfunction "2_2") (pintype "passive"))
      (node (ref "C5") (pin "1") (pinfunction "1_1") (pintype "passive"))
      (node (ref "C6") (pin "1") (pinfunction "1_1") (pintype "passive"))
      (node (ref "C8") (pin "2") (pinfunction "2_2") (pintype "passive"))
      (node (ref "C9") (pin "1") (pinfunction "1_1") (pintype "passive"))
      (node (ref "IC1") (pin "22") (pinfunction "AGND_22") (pintype "bidirectional"))
      (node (ref "IC1") (pin "8") (pinfunction "GND_8") (pintype "bidirectional"))
      (node (ref "IC2") (pin "22") (pinfunction "AGND_22") (pintype "bidirectional"))
      (node (ref "IC2") (pin "8") (pinfunction "GND_8") (pintype "bidirectional"))
      (node (ref "IC6") (pin "20") (pinfunction "GND_20") (pintype "bidirectional"))
      (node (ref "JP1") (pin "1") (pinfunction "1_1") (pintype "passive"))
      (node (ref "JP3") (pin "6") (pinfunction "6_6") (pintype "passive"))
      (node (ref "LASEROUT1") (pin "1") (pinfunction "KL_1") (pintype "passive"))
      (node (ref "OKCHILL") (pin "K") (pinfunction "C_K") (pintype "passive"))
      (node (ref "OKDOOR") (pin "K") (pinfunction "C_K") (pintype "passive"))
      (node (ref "OKLIM1") (pin "K") (pinfunction "C_K") (pintype "passive"))
      (node (ref "OKLIM2") (pin "K") (pinfunction "C_K") (pintype "passive"))
      (node (ref "Q5") (pin "S") (pinfunction "S_S") (pintype "passive"))
      (node (ref "R15") (pin "1") (pinfunction "1_1") (pintype "passive"))
      (node (ref "R18") (pin "1") (pinfunction "1_1") (pintype "passive"))
      (node (ref "R3") (pin "2") (pinfunction "2_2") (pintype "passive"))
      (node (ref "S1") (pin "3") (pinfunction "3_3") (pintype "passive"))
      (node (ref "S1") (pin "4") (pinfunction "4_4") (pintype "passive"))
      (node (ref "TH_ON") (pin "K") (pinfunction "C_K") (pintype "passive"))
      (node (ref "V1") (pin "7") (pinfunction "-UB_7") (pintype "power_in"))
      (node (ref "V2") (pin "7") (pinfunction "-UB_7") (pintype "power_in"))
      (node (ref "VCCOK") (pin "K") (pinfunction "C_K") (pintype "passive"))
      (node (ref "WATERTEMP") (pin "2") (pinfunction "KL_2") (pintype "passive"))
      (node (ref "X1") (pin "1") (pinfunction "S_1") (pintype "passive"))
      (node (ref "X3") (pin "GND") (pinfunction "GND_GND") (pintype "bidirectional"))
      (node (ref "XDIR") (pin "2") (pinfunction "KL_2") (pintype "passive"))
      (node (ref "XDIRLED") (pin "K") (pinfunction "C_K") (pintype "passive"))
      (node (ref "XMAX") (pin "1") (pinfunction "KL_1") (pintype "passive"))
      (node (ref "XMIN") (pin "1") (pinfunction "KL_1") (pintype "passive"))
      (node (ref "XSTEP") (pin "2") (pinfunction "KL_2") (pintype "passive"))
      (node (ref "XSTEPLED") (pin "K") (pinfunction "C_K") (pintype "passive"))
      (node (ref "YDIR") (pin "2") (pinfunction "KL_2") (pintype "passive"))
      (node (ref "YDIRLED") (pin "K") (pinfunction "C_K") (pintype "passive"))
      (node (ref "YMAX") (pin "1") (pinfunction "KL_1") (pintype "passive"))
      (node (ref "YMIN") (pin "1") (pinfunction "KL_1") (pintype "passive"))
      (node (ref "YSTEP") (pin "2") (pinfunction "KL_2") (pintype "passive"))
      (node (ref "YSTEPLED") (pin "K") (pinfunction "C_K") (pintype "passive"))
      (node (ref "ZDIR") (pin "2") (pinfunction "KL_2") (pintype "passive"))
      (node (ref "ZMAX") (pin "1") (pinfunction "KL_1") (pintype "passive"))
      (node (ref "ZMIN") (pin "1") (pinfunction "KL_1") (pintype "passive"))
      (node (ref "ZSTEP") (pin "2") (pinfunction "KL_2") (pintype "passive"))
    )
    (net (code "50") (name "Net-(AIR-ON-PadA)") (class "Default")
      (node (ref "AIR-ON") (pin "A") (pinfunction "A_A") (pintype "passive"))
      (node (ref "R59") (pin "1") (pinfunction "1_1") (pintype "passive"))
    )
    (net (code "51") (name "Net-(AUX1-Pad1)") (class "Default")
      (node (ref "AUX1") (pin "1") (pinfunction "1_1") (pintype "passive"))
      (node (ref "R2") (pin "2") (pinfunction "2_2") (pintype "passive"))
    )
    (net (code "52") (name "Net-(FXM-PadA)") (class "Default")
      (node (ref "FXM") (pin "A") (pinfunction "A_A") (pintype "passive"))
      (node (ref "R25") (pin "1") (pinfunction "1_1") (pintype "passive"))
    )
    (net (code "53") (name "Net-(FXP-PadA)") (class "Default")
      (node (ref "FXP") (pin "A") (pinfunction "A_A") (pintype "passive"))
      (node (ref "R26") (pin "1") (pinfunction "1_1") (pintype "passive"))
    )
    (net (code "54") (name "Net-(FYM-PadA)") (class "Default")
      (node (ref "FYM") (pin "A") (pinfunction "A_A") (pintype "passive"))
      (node (ref "R27") (pin "1") (pinfunction "1_1") (pintype "passive"))
    )
    (net (code "55") (name "Net-(FYP-PadA)") (class "Default")
      (node (ref "FYP") (pin "A") (pinfunction "A_A") (pintype "passive"))
      (node (ref "R28") (pin "1") (pinfunction "1_1") (pintype "passive"))
    )
    (net (code "56") (name "Net-(FZM-PadA)") (class "Default")
      (node (ref "FZM") (pin "A") (pinfunction "A_A") (pintype "passive"))
      (node (ref "R29") (pin "1") (pinfunction "1_1") (pintype "passive"))
    )
    (net (code "57") (name "Net-(FZP-PadA)") (class "Default")
      (node (ref "FZP") (pin "A") (pinfunction "A_A") (pintype "passive"))
      (node (ref "R30") (pin "1") (pinfunction "1_1") (pintype "passive"))
    )
    (net (code "58") (name "Net-(IC1-PB6(XTAL1{slash}TOSC1{slash}PCI6))") (class "Default")
      (node (ref "C1") (pin "1") (pinfunction "1_1") (pintype "passive"))
      (node (ref "IC1") (pin "9") (pinfunction "PB6(XTAL1/TOSC1/PCI6)_9") (pintype "bidirectional"))
      (node (ref "Y1") (pin "2") (pinfunction "2_2") (pintype "passive"))
    )
    (net (code "59") (name "Net-(IC1-PB7(XTAL2{slash}TOSC2{slash}PCI7))") (class "Default")
      (node (ref "C2") (pin "1") (pinfunction "1_1") (pintype "passive"))
      (node (ref "IC1") (pin "10") (pinfunction "PB7(XTAL2/TOSC2/PCI7)_10") (pintype "bidirectional"))
      (node (ref "Y1") (pin "1") (pinfunction "1_1") (pintype "passive"))
    )
    (net (code "60") (name "Net-(IC2-PB6(XTAL1{slash}TOSC1{slash}PCI6))") (class "Default")
      (node (ref "C8") (pin "1") (pinfunction "1_1") (pintype "passive"))
      (node (ref "IC2") (pin "9") (pinfunction "PB6(XTAL1/TOSC1/PCI6)_9") (pintype "bidirectional"))
      (node (ref "Y2") (pin "2") (pinfunction "2_2") (pintype "passive"))
    )
    (net (code "61") (name "Net-(IC2-PB7(XTAL2{slash}TOSC2{slash}PCI7))") (class "Default")
      (node (ref "C12") (pin "1") (pinfunction "1_1") (pintype "passive"))
      (node (ref "IC2") (pin "10") (pinfunction "PB7(XTAL2/TOSC2/PCI7)_10") (pintype "bidirectional"))
      (node (ref "Y2") (pin "1") (pinfunction "1_1") (pintype "passive"))
    )
    (net (code "62") (name "Net-(IC6-D+)") (class "Default")
      (node (ref "IC6") (pin "19") (pinfunction "D+_19") (pintype "bidirectional"))
      (node (ref "X3") (pin "D+") (pinfunction "D+_D+") (pintype "bidirectional"))
    )
    (net (code "63") (name "Net-(IC6-D-)") (class "Default")
      (node (ref "IC6") (pin "18") (pinfunction "D-_18") (pintype "bidirectional"))
      (node (ref "X3") (pin "D-") (pinfunction "D-_D-") (pintype "bidirectional"))
    )
    (net (code "64") (name "Net-(IC6-OSC1)") (class "Default")
      (node (ref "C41") (pin "2") (pinfunction "2_2") (pintype "passive"))
      (node (ref "IC6") (pin "2") (pinfunction "OSC1_2") (pintype "bidirectional"))
      (node (ref "Q8") (pin "1") (pinfunction "1_1") (pintype "passive"))
    )
    (net (code "65") (name "Net-(IC6-OSC2)") (class "Default")
      (node (ref "C40") (pin "1") (pinfunction "1_1") (pintype "passive"))
      (node (ref "IC6") (pin "3") (pinfunction "OSC2_3") (pintype "bidirectional"))
      (node (ref "Q8") (pin "2") (pinfunction "2_2") (pintype "passive"))
    )
    (net (code "66") (name "Net-(IC6-RST)") (class "Default")
      (node (ref "IC6") (pin "4") (pinfunction "RST_4") (pintype "bidirectional"))
      (node (ref "R47") (pin "1") (pinfunction "1_1") (pintype "passive"))
    )
    (net (code "67") (name "Net-(IC6-RX)") (class "Default")
      (node (ref "IC6") (pin "12") (pinfunction "RX_12") (pintype "bidirectional"))
      (node (ref "SJ2") (pin "1") (pinfunction "1_1") (pintype "passive"))
    )
    (net (code "68") (name "Net-(IC6-RXLED)") (class "Default")
      (node (ref "IC6") (pin "6") (pinfunction "RXLED_6") (pintype "bidirectional"))
      (node (ref "R49") (pin "2") (pinfunction "2_2") (pintype "passive"))
    )
    (net (code "69") (name "Net-(IC6-TX)") (class "Default")
      (node (ref "IC6") (pin "10") (pinfunction "TX_10") (pintype "bidirectional"))
      (node (ref "SJ1") (pin "1") (pinfunction "1_1") (pintype "passive"))
    )
    (net (code "70") (name "Net-(IC6-VUSB)") (class "Default")
      (node (ref "C42") (pin "2") (pinfunction "2_2") (pintype "passive"))
      (node (ref "IC6") (pin "17") (pinfunction "VUSB_17") (pintype "bidirectional"))
    )
    (net (code "71") (name "Net-(OKCHILL-PadA)") (class "Default")
      (node (ref "OKCHILL") (pin "A") (pinfunction "A_A") (pintype "passive"))
      (node (ref "R20") (pin "1") (pinfunction "1_1") (pintype "passive"))
    )
    (net (code "72") (name "Net-(OKDOOR-PadA)") (class "Default")
      (node (ref "OKDOOR") (pin "A") (pinfunction "A_A") (pintype "passive"))
      (node (ref "R19") (pin "1") (pinfunction "1_1") (pintype "passive"))
    )
    (net (code "73") (name "Net-(OKLIM1-PadA)") (class "Default")
      (node (ref "OKLIM1") (pin "A") (pinfunction "A_A") (pintype "passive"))
      (node (ref "R12") (pin "1") (pinfunction "1_1") (pintype "passive"))
    )
    (net (code "74") (name "Net-(OKLIM2-PadA)") (class "Default")
      (node (ref "OKLIM2") (pin "A") (pinfunction "A_A") (pintype "passive"))
      (node (ref "R14") (pin "1") (pinfunction "1_1") (pintype "passive"))
    )
    (net (code "75") (name "Net-(OKWP-PadA)") (class "Default")
      (node (ref "OKWP") (pin "A") (pinfunction "A_A") (pintype "passive"))
      (node (ref "R22") (pin "1") (pinfunction "1_1") (pintype "passive"))
    )
    (net (code "76") (name "Net-(Q5-PadG)") (class "Default")
      (node (ref "Q5") (pin "G") (pinfunction "G_G") (pintype "passive"))
      (node (ref "R58") (pin "2") (pinfunction "2_2") (pintype "passive"))
    )
    (net (code "77") (name "Net-(R11-Pad1)") (class "Default")
      (node (ref "R11") (pin "1") (pinfunction "1_1") (pintype "passive"))
      (node (ref "XSTEPLED") (pin "A") (pinfunction "A_A") (pintype "passive"))
    )
    (net (code "78") (name "Net-(R16-Pad1)") (class "Default")
      (node (ref "R16") (pin "1") (pinfunction "1_1") (pintype "passive"))
      (node (ref "XDIRLED") (pin "A") (pinfunction "A_A") (pintype "passive"))
    )
    (net (code "79") (name "Net-(R17-Pad1)") (class "Default")
      (node (ref "R17") (pin "1") (pinfunction "1_1") (pintype "passive"))
      (node (ref "YSTEPLED") (pin "A") (pinfunction "A_A") (pintype "passive"))
    )
    (net (code "80") (name "Net-(R21-Pad1)") (class "Default")
      (node (ref "R21") (pin "1") (pinfunction "1_1") (pintype "passive"))
      (node (ref "YDIRLED") (pin "A") (pinfunction "A_A") (pintype "passive"))
    )
    (net (code "81") (name "Net-(R23-Pad1)") (class "Default")
      (node (ref "R23") (pin "1") (pinfunction "1_1") (pintype "passive"))
      (node (ref "TH_ON") (pin "A") (pinfunction "A_A") (pintype "passive"))
    )
    (net (code "82") (name "Net-(R24-Pad1)") (class "Default")
      (node (ref "R24") (pin "1") (pinfunction "1_1") (pintype "passive"))
      (node (ref "VCCOK") (pin "A") (pinfunction "A_A") (pintype "passive"))
    )
    (net (code "83") (name "Net-(R49-Pad1)") (class "Default")
      (node (ref "R49") (pin "1") (pinfunction "1_1") (pintype "passive"))
      (node (ref "TXLED3") (pin "C") (pinfunction "C_C") (pintype "passive"))
    )
    (net (code "84") (name "Net-(V1E-A)") (class "Default")
      (node (ref "R13") (pin "2") (pinfunction "2_2") (pintype "passive"))
      (node (ref "V1") (pin "9") (pinfunction "A_9") (pintype "input"))
    )
    (net (code "85") (name "Net-(V2C-C)") (class "Default")
      (node (ref "V2") (pin "13") (pinfunction "C_13") (pintype "input"))
      (node (ref "V2") (pin "6") (pinfunction "Y_6") (pintype "output"))
    )
    (net (code "86") (name "Net-(V2C-Y)") (class "Default")
      (node (ref "V2") (pin "11") (pinfunction "C_11") (pintype "input"))
      (node (ref "V2") (pin "12") (pinfunction "Y_12") (pintype "output"))
    )
    (net (code "87") (name "unconnected-(IC6-CTS-Pad13)") (class "Default")
      (node (ref "IC6") (pin "13") (pinfunction "CTS_13") (pintype "bidirectional"))
    )
    (net (code "88") (name "unconnected-(IC6-GPIO2-Pad14)") (class "Default")
      (node (ref "IC6") (pin "14") (pinfunction "GPIO2_14") (pintype "bidirectional"))
    )
    (net (code "89") (name "unconnected-(IC6-GPIO3-Pad9)") (class "Default")
      (node (ref "IC6") (pin "9") (pinfunction "GPIO3_9") (pintype "bidirectional"))
    )
    (net (code "90") (name "unconnected-(IC6-GPIO4-Pad8)") (class "Default")
      (node (ref "IC6") (pin "8") (pinfunction "GPIO4_8") (pintype "bidirectional"))
    )
    (net (code "91") (name "unconnected-(IC6-GPIO5-Pad7)") (class "Default")
      (node (ref "IC6") (pin "7") (pinfunction "GPIO5_7") (pintype "bidirectional"))
    )
    (net (code "92") (name "unconnected-(IC6-SSPND-Pad16)") (class "Default")
      (node (ref "IC6") (pin "16") (pinfunction "SSPND_16") (pintype "bidirectional"))
    )
    (net (code "93") (name "unconnected-(IC6-TXLED-Pad5)") (class "Default")
      (node (ref "IC6") (pin "5") (pinfunction "TXLED_5") (pintype "bidirectional"))
    )
    (net (code "94") (name "unconnected-(IC6-USBCFG-Pad15)") (class "Default")
      (node (ref "IC6") (pin "15") (pinfunction "USBCFG_15") (pintype "bidirectional"))
    )
    (net (code "95") (name "unconnected-(JP1-Pad3)") (class "Default")
      (node (ref "JP1") (pin "3") (pinfunction "3_3") (pintype "passive"))
    )
    (net (code "96") (name "unconnected-(JP3-Pad8)") (class "Default")
      (node (ref "JP3") (pin "8") (pinfunction "8_8") (pintype "passive"))
    )
  )
)
